# ActuatorTop.net
KiCad netlist of a schematic drawn in Altium Designer
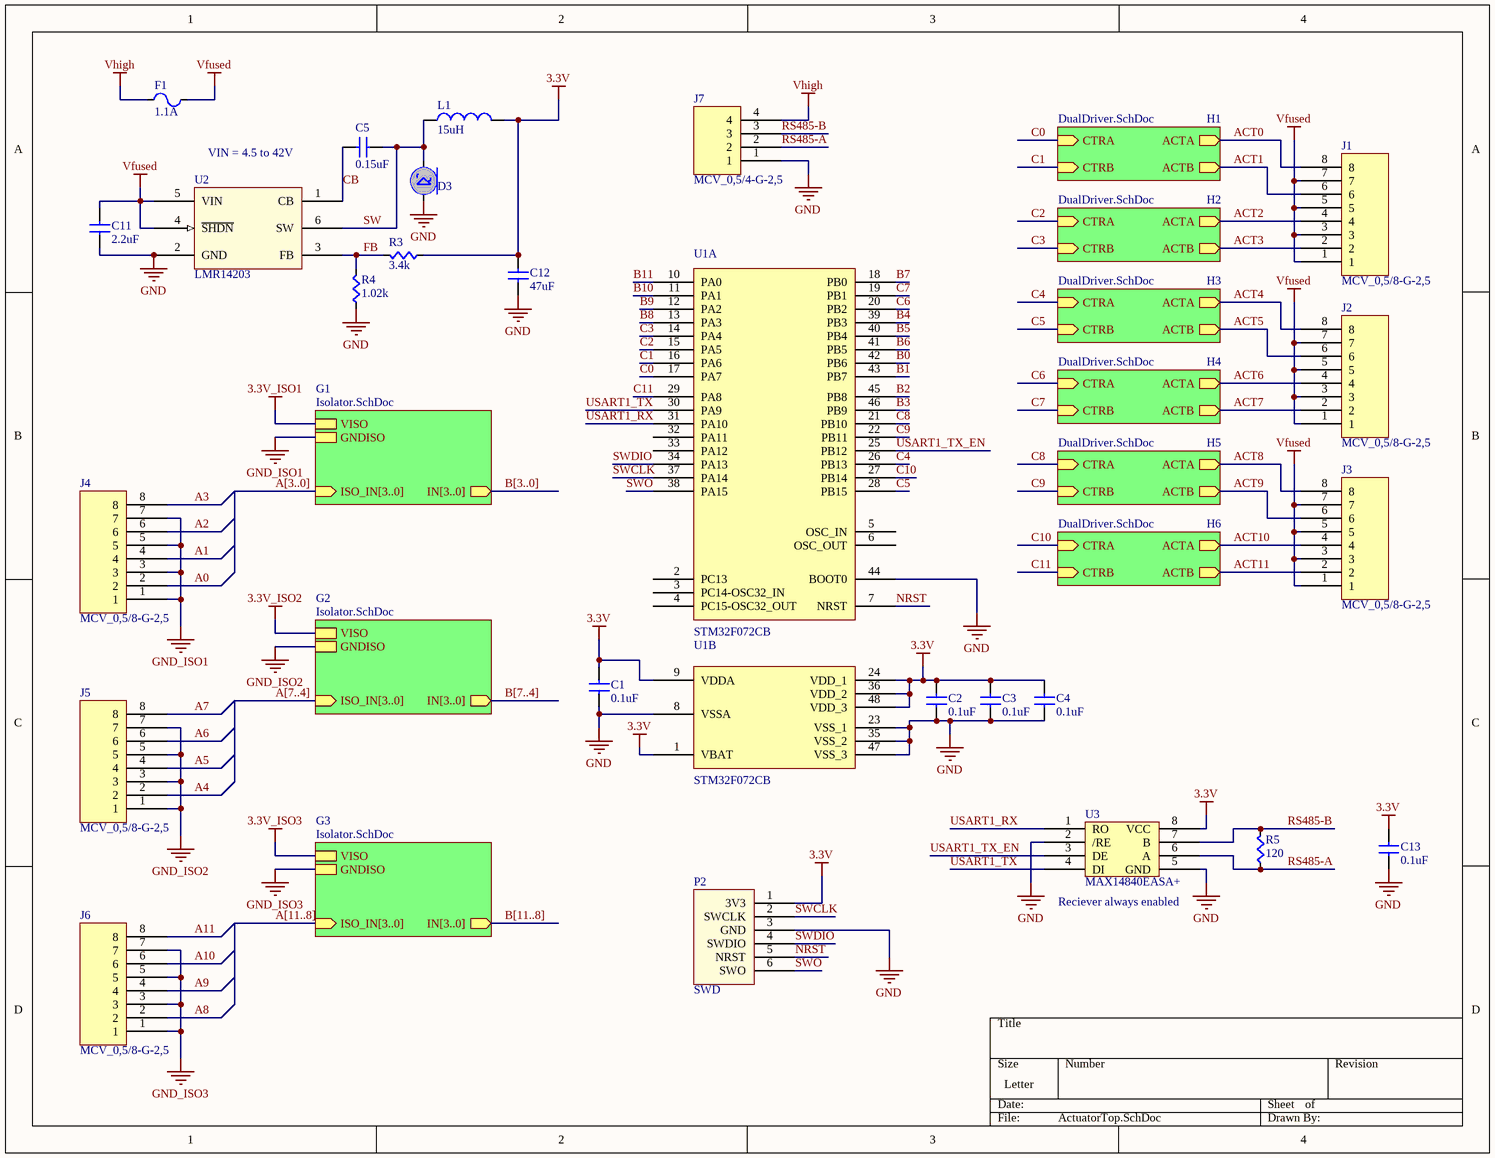
[diagram p0: ActuatorTop.SchDoc]

(export (version "E")
  (design (tool "Eeschema 10.0.6"))
  (components
    (comp (ref "C1")
      (value "0.1uF")
      (footprint "CAPC0603")
      (fields (field (name "Comment") "Cap"))
      (libsource (lib "Passives") (part "Cap"))
    )
    (comp (ref "C2")
      (value "0.1uF")
      (footprint "CAPC0603")
      (fields (field (name "Comment") "Cap"))
      (libsource (lib "Passives") (part "Cap"))
    )
    (comp (ref "C3")
      (value "0.1uF")
      (footprint "CAPC0603")
      (fields (field (name "Comment") "Cap"))
      (libsource (lib "Passives") (part "Cap"))
    )
    (comp (ref "C4")
      (value "0.1uF")
      (footprint "CAPC0603")
      (fields (field (name "Comment") "Cap"))
      (libsource (lib "Passives") (part "Cap"))
    )
    (comp (ref "C5")
      (value "0.15uF")
      (footprint "CAPC0603")
      (fields (field (name "Comment") "Cap"))
      (libsource (lib "Passives") (part "Cap"))
    )
    (comp (ref "C11")
      (value "2.2uF")
      (footprint "CAPC0805")
      (fields (field (name "Comment") "Cap"))
      (libsource (lib "Passives") (part "Cap"))
    )
    (comp (ref "C12")
      (value "47uF")
      (footprint "CAPC1206")
      (fields (field (name "Comment") "Cap"))
      (libsource (lib "Passives") (part "Cap"))
    )
    (comp (ref "C13")
      (value "0.1uF")
      (footprint "CAPC0603")
      (fields (field (name "Comment") "Cap"))
      (libsource (lib "Passives") (part "Cap"))
    )
    (comp (ref "D3")
      (value "Schottky")
      (footprint "1N5819HW-7-F")
      (description "Schottky Diode Template")
      (libsource (lib "Semiconductors") (part "Schottky"))
    )
    (comp (ref "F1")
      (value "1.1A")
      (footprint "PTC7451X11N")
      (fields (field (name "Comment") "PTC Fuse"))
      (libsource (lib "Passives") (part "PTC_Fuse"))
    )
    (comp (ref "J1")
      (value "MCV_0,5/8-G-2,5")
      (footprint "MCV_0,5/8-G-2,5")
      (description "CONN TERM BLOCK 2.50MM 8POS, Vertical, Through-Hole, 4A")
      (libsource (lib "") (part "MCV_0,5/8-G-2,5_1"))
    )
    (comp (ref "J2")
      (value "MCV_0,5/8-G-2,5")
      (footprint "MCV_0,5/8-G-2,5")
      (description "CONN TERM BLOCK 2.50MM 8POS, Vertical, Through-Hole, 4A")
      (libsource (lib "") (part "MCV_0,5/8-G-2,5_1"))
    )
    (comp (ref "J3")
      (value "MCV_0,5/8-G-2,5")
      (footprint "MCV_0,5/8-G-2,5")
      (description "CONN TERM BLOCK 2.50MM 8POS, Vertical, Through-Hole, 4A")
      (libsource (lib "") (part "MCV_0,5/8-G-2,5_1"))
    )
    (comp (ref "J4")
      (value "MCV_0,5/8-G-2,5")
      (footprint "MCV_0,5/8-G-2,5")
      (description "CONN TERM BLOCK 2.50MM 8POS, Vertical, Through-Hole, 4A")
      (libsource (lib "Connectors") (part "MCV_0,5/8-G-2,5"))
    )
    (comp (ref "J5")
      (value "MCV_0,5/8-G-2,5")
      (footprint "MCV_0,5/8-G-2,5")
      (description "CONN TERM BLOCK 2.50MM 8POS, Vertical, Through-Hole, 4A")
      (libsource (lib "Connectors") (part "MCV_0,5/8-G-2,5"))
    )
    (comp (ref "J6")
      (value "MCV_0,5/8-G-2,5")
      (footprint "MCV_0,5/8-G-2,5")
      (description "CONN TERM BLOCK 2.50MM 8POS, Vertical, Through-Hole, 4A")
      (libsource (lib "Connectors") (part "MCV_0,5/8-G-2,5"))
    )
    (comp (ref "J7")
      (value "MCV_0,5/4-G-2,5")
      (footprint "MCV_0,5/4-G-2,5")
      (description "CONN TERM BLOCK 2.50MM 4POS, Vertical, Through-Hole, 4A")
      (libsource (lib "Connectors") (part "MCV_0,5/4-G-2,5"))
    )
    (comp (ref "L1")
      (value "Inductor")
      (footprint "INDP6060X48N")
      (fields (field (name "INDUCTANCE") "15uH"))
      (libsource (lib "Passives") (part "Inductor"))
    )
    (comp (ref "P2")
      (value "SWD")
      (footprint "SWD_STM32")
      (description "SWD connector matching the pinout on STM Discovery Boards")
      (libsource (lib "Connectors") (part "SWD_STM32"))
    )
    (comp (ref "R3")
      (value "3.4k")
      (footprint "RES0603")
      (fields (field (name "Comment") "Res"))
      (libsource (lib "Passives") (part "Res"))
    )
    (comp (ref "R4")
      (value "1.02k")
      (footprint "RES0603")
      (fields (field (name "Comment") "Res"))
      (libsource (lib "Passives") (part "Res"))
    )
    (comp (ref "R5")
      (value "120")
      (footprint "RES0603")
      (fields (field (name "Comment") "Res"))
      (libsource (lib "Passives") (part "Res"))
    )
    (comp (ref "U1")
      (value "STM32F072CB")
      (footprint "STM32F072CB")
      (description "MCU 32BIT 128KB FLASH 48LQFP")
      (libsource (lib "ICs") (part "STM32F072CB"))
    )
    (comp (ref "U2")
      (value "LMR14203")
      (footprint "SOT95P280X110-6N")
      (description "Simple Switcher 42Vin 0.3A Step-Down Voltage Regulator")
      (libsource (lib "ICs") (part "LMR14203"))
    )
    (comp (ref "U3")
      (value "MAX14840EASA+")
      (footprint "MAX14840EASA+")
      (description "TXRX 40MBPS RS485/RS422 8-SOIC")
      (libsource (lib "ICs") (part "MAX14840EASA+"))
    )
  )
  (nets
    (net (code "1") (name "/A0") (class "Default")
      (node (ref "J4") (pin "2") (pinfunction "2_2") (pintype "passive"))
    )
    (net (code "2") (name "/A1") (class "Default")
      (node (ref "J4") (pin "4") (pinfunction "4_4") (pintype "passive"))
    )
    (net (code "3") (name "/A2") (class "Default")
      (node (ref "J4") (pin "6") (pinfunction "6_6") (pintype "passive"))
    )
    (net (code "4") (name "/A3") (class "Default")
      (node (ref "J4") (pin "8") (pinfunction "8_8") (pintype "passive"))
    )
    (net (code "5") (name "/A4") (class "Default")
      (node (ref "J5") (pin "2") (pinfunction "2_2") (pintype "passive"))
    )
    (net (code "6") (name "/A5") (class "Default")
      (node (ref "J5") (pin "4") (pinfunction "4_4") (pintype "passive"))
    )
    (net (code "7") (name "/A6") (class "Default")
      (node (ref "J5") (pin "6") (pinfunction "6_6") (pintype "passive"))
    )
    (net (code "8") (name "/A7") (class "Default")
      (node (ref "J5") (pin "8") (pinfunction "8_8") (pintype "passive"))
    )
    (net (code "9") (name "/A8") (class "Default")
      (node (ref "J6") (pin "2") (pinfunction "2_2") (pintype "passive"))
    )
    (net (code "10") (name "/A9") (class "Default")
      (node (ref "J6") (pin "4") (pinfunction "4_4") (pintype "passive"))
    )
    (net (code "11") (name "/A10") (class "Default")
      (node (ref "J6") (pin "6") (pinfunction "6_6") (pintype "passive"))
    )
    (net (code "12") (name "/A11") (class "Default")
      (node (ref "J6") (pin "8") (pinfunction "8_8") (pintype "passive"))
    )
    (net (code "13") (name "/ACT0") (class "Default")
      (node (ref "J1") (pin "8") (pinfunction "8_8") (pintype "passive"))
    )
    (net (code "14") (name "/ACT1") (class "Default")
      (node (ref "J1") (pin "6") (pinfunction "6_6") (pintype "passive"))
    )
    (net (code "15") (name "/ACT2") (class "Default")
      (node (ref "J1") (pin "4") (pinfunction "4_4") (pintype "passive"))
    )
    (net (code "16") (name "/ACT3") (class "Default")
      (node (ref "J1") (pin "2") (pinfunction "2_2") (pintype "passive"))
    )
    (net (code "17") (name "/ACT4") (class "Default")
      (node (ref "J2") (pin "8") (pinfunction "8_8") (pintype "passive"))
    )
    (net (code "18") (name "/ACT5") (class "Default")
      (node (ref "J2") (pin "6") (pinfunction "6_6") (pintype "passive"))
    )
    (net (code "19") (name "/ACT6") (class "Default")
      (node (ref "J2") (pin "4") (pinfunction "4_4") (pintype "passive"))
    )
    (net (code "20") (name "/ACT7") (class "Default")
      (node (ref "J2") (pin "2") (pinfunction "2_2") (pintype "passive"))
    )
    (net (code "21") (name "/ACT8") (class "Default")
      (node (ref "J3") (pin "8") (pinfunction "8_8") (pintype "passive"))
    )
    (net (code "22") (name "/ACT9") (class "Default")
      (node (ref "J3") (pin "6") (pinfunction "6_6") (pintype "passive"))
    )
    (net (code "23") (name "/ACT10") (class "Default")
      (node (ref "J3") (pin "4") (pinfunction "4_4") (pintype "passive"))
    )
    (net (code "24") (name "/ACT11") (class "Default")
      (node (ref "J3") (pin "2") (pinfunction "2_2") (pintype "passive"))
    )
    (net (code "28") (name "/B0") (class "Default")
      (node (ref "U1") (pin "42") (pinfunction "PB6_42") (pintype "passive"))
    )
    (net (code "29") (name "/B1") (class "Default")
      (node (ref "U1") (pin "43") (pinfunction "PB7_43") (pintype "passive"))
    )
    (net (code "30") (name "/B2") (class "Default")
      (node (ref "U1") (pin "45") (pinfunction "PB8_45") (pintype "passive"))
    )
    (net (code "31") (name "/B3") (class "Default")
      (node (ref "U1") (pin "46") (pinfunction "PB9_46") (pintype "passive"))
    )
    (net (code "32") (name "/B4") (class "Default")
      (node (ref "U1") (pin "39") (pinfunction "PB3_39") (pintype "passive"))
    )
    (net (code "33") (name "/B5") (class "Default")
      (node (ref "U1") (pin "40") (pinfunction "PB4_40") (pintype "passive"))
    )
    (net (code "34") (name "/B6") (class "Default")
      (node (ref "U1") (pin "41") (pinfunction "PB5_41") (pintype "passive"))
    )
    (net (code "35") (name "/B7") (class "Default")
      (node (ref "U1") (pin "18") (pinfunction "PB0_18") (pintype "passive"))
    )
    (net (code "36") (name "/B8") (class "Default")
      (node (ref "U1") (pin "13") (pinfunction "PA3_13") (pintype "passive"))
    )
    (net (code "37") (name "/B9") (class "Default")
      (node (ref "U1") (pin "12") (pinfunction "PA2_12") (pintype "passive"))
    )
    (net (code "38") (name "/B10") (class "Default")
      (node (ref "U1") (pin "11") (pinfunction "PA1_11") (pintype "passive"))
    )
    (net (code "39") (name "/B11") (class "Default")
      (node (ref "U1") (pin "10") (pinfunction "PA0_10") (pintype "passive"))
    )
    (net (code "43") (name "/C0") (class "Default")
      (node (ref "U1") (pin "17") (pinfunction "PA7_17") (pintype "passive"))
    )
    (net (code "44") (name "/C1") (class "Default")
      (node (ref "U1") (pin "16") (pinfunction "PA6_16") (pintype "passive"))
    )
    (net (code "45") (name "/C2") (class "Default")
      (node (ref "U1") (pin "15") (pinfunction "PA5_15") (pintype "passive"))
    )
    (net (code "46") (name "/C3") (class "Default")
      (node (ref "U1") (pin "14") (pinfunction "PA4_14") (pintype "passive"))
    )
    (net (code "47") (name "/C4") (class "Default")
      (node (ref "U1") (pin "26") (pinfunction "PB13_26") (pintype "passive"))
    )
    (net (code "48") (name "/C5") (class "Default")
      (node (ref "U1") (pin "28") (pinfunction "PB15_28") (pintype "passive"))
    )
    (net (code "49") (name "/C6") (class "Default")
      (node (ref "U1") (pin "20") (pinfunction "PB2_20") (pintype "passive"))
    )
    (net (code "50") (name "/C7") (class "Default")
      (node (ref "U1") (pin "19") (pinfunction "PB1_19") (pintype "passive"))
    )
    (net (code "51") (name "/C8") (class "Default")
      (node (ref "U1") (pin "21") (pinfunction "PB10_21") (pintype "passive"))
    )
    (net (code "52") (name "/C9") (class "Default")
      (node (ref "U1") (pin "22") (pinfunction "PB11_22") (pintype "passive"))
    )
    (net (code "53") (name "/C10") (class "Default")
      (node (ref "U1") (pin "27") (pinfunction "PB14_27") (pintype "passive"))
    )
    (net (code "54") (name "/C11") (class "Default")
      (node (ref "U1") (pin "29") (pinfunction "PA8_29") (pintype "passive"))
    )
    (net (code "55") (name "/CB") (class "Default")
      (node (ref "C5") (pin "1") (pinfunction "A_1") (pintype "passive"))
      (node (ref "U2") (pin "1") (pinfunction "CB_1") (pintype "passive"))
    )
    (net (code "56") (name "/FB") (class "Default")
      (node (ref "R3") (pin "1") (pinfunction "A_1") (pintype "passive"))
      (node (ref "R4") (pin "1") (pinfunction "A_1") (pintype "passive"))
      (node (ref "U2") (pin "3") (pinfunction "FB_3") (pintype "passive"))
    )
    (net (code "57") (name "/NRST") (class "Default")
      (node (ref "P2") (pin "5") (pinfunction "NRST_5") (pintype "passive"))
      (node (ref "U1") (pin "7") (pinfunction "NRST_7") (pintype "passive"))
    )
    (net (code "58") (name "/RS485-A") (class "Default")
      (node (ref "J7") (pin "2") (pinfunction "2_2") (pintype "passive"))
      (node (ref "R5") (pin "2") (pinfunction "B_2") (pintype "passive"))
      (node (ref "U3") (pin "6") (pinfunction "A_6") (pintype "passive"))
    )
    (net (code "59") (name "/RS485-B") (class "Default")
      (node (ref "J7") (pin "3") (pinfunction "3_3") (pintype "passive"))
      (node (ref "R5") (pin "1") (pinfunction "A_1") (pintype "passive"))
      (node (ref "U3") (pin "7") (pinfunction "B_7") (pintype "passive"))
    )
    (net (code "60") (name "/SW") (class "Default")
      (node (ref "C5") (pin "2") (pinfunction "B_2") (pintype "passive"))
      (node (ref "D3") (pin "C") (pinfunction "C_C") (pintype "passive"))
      (node (ref "L1") (pin "1") (pinfunction "A_1") (pintype "passive"))
      (node (ref "U2") (pin "6") (pinfunction "SW_6") (pintype "passive"))
    )
    (net (code "61") (name "/SWCLK") (class "Default")
      (node (ref "P2") (pin "2") (pinfunction "SWCLK_2") (pintype "passive"))
      (node (ref "U1") (pin "37") (pinfunction "PA14_37") (pintype "passive"))
    )
    (net (code "62") (name "/SWDIO") (class "Default")
      (node (ref "P2") (pin "4") (pinfunction "SWDIO_4") (pintype "passive"))
      (node (ref "U1") (pin "34") (pinfunction "PA13_34") (pintype "passive"))
    )
    (net (code "63") (name "/SWO") (class "Default")
      (node (ref "P2") (pin "6") (pinfunction "SWO_6") (pintype "passive"))
      (node (ref "U1") (pin "38") (pinfunction "PA15_38") (pintype "passive"))
    )
    (net (code "64") (name "/USART1_RX") (class "Default")
      (node (ref "U1") (pin "31") (pinfunction "PA10_31") (pintype "passive"))
      (node (ref "U3") (pin "1") (pinfunction "RO_1") (pintype "passive"))
    )
    (net (code "65") (name "/USART1_TX") (class "Default")
      (node (ref "U1") (pin "30") (pinfunction "PA9_30") (pintype "passive"))
      (node (ref "U3") (pin "4") (pinfunction "DI_4") (pintype "passive"))
    )
    (net (code "66") (name "/USART1_TX_EN") (class "Default")
      (node (ref "U1") (pin "25") (pinfunction "PB12_25") (pintype "passive"))
      (node (ref "U3") (pin "3") (pinfunction "DE_3") (pintype "passive"))
    )
    (net (code "67") (name "3.3V") (class "Default")
      (node (ref "C1") (pin "1") (pinfunction "A_1") (pintype "passive"))
      (node (ref "C12") (pin "2") (pinfunction "B_2") (pintype "passive"))
      (node (ref "C13") (pin "1") (pinfunction "A_1") (pintype "passive"))
      (node (ref "C2") (pin "1") (pinfunction "A_1") (pintype "passive"))
      (node (ref "C3") (pin "1") (pinfunction "A_1") (pintype "passive"))
      (node (ref "C4") (pin "1") (pinfunction "A_1") (pintype "passive"))
      (node (ref "L1") (pin "2") (pinfunction "B_2") (pintype "passive"))
      (node (ref "P2") (pin "1") (pinfunction "3V3_1") (pintype "passive"))
      (node (ref "R3") (pin "2") (pinfunction "B_2") (pintype "passive"))
      (node (ref "U1") (pin "1") (pinfunction "VBAT_1") (pintype "passive"))
      (node (ref "U1") (pin "24") (pinfunction "VDD_1_24") (pintype "passive"))
      (node (ref "U1") (pin "36") (pinfunction "VDD_2_36") (pintype "passive"))
      (node (ref "U1") (pin "48") (pinfunction "VDD_3_48") (pintype "passive"))
      (node (ref "U1") (pin "9") (pinfunction "VDDA_9") (pintype "passive"))
      (node (ref "U3") (pin "8") (pinfunction "VCC_8") (pintype "passive"))
    )
    (net (code "71") (name "GND") (class "Default")
      (node (ref "C1") (pin "2") (pinfunction "B_2") (pintype "passive"))
      (node (ref "C11") (pin "1") (pinfunction "A_1") (pintype "passive"))
      (node (ref "C12") (pin "1") (pinfunction "A_1") (pintype "passive"))
      (node (ref "C13") (pin "2") (pinfunction "B_2") (pintype "passive"))
      (node (ref "C2") (pin "2") (pinfunction "B_2") (pintype "passive"))
      (node (ref "C3") (pin "2") (pinfunction "B_2") (pintype "passive"))
      (node (ref "C4") (pin "2") (pinfunction "B_2") (pintype "passive"))
      (node (ref "D3") (pin "A") (pinfunction "A_A") (pintype "passive"))
      (node (ref "J7") (pin "1") (pinfunction "1_1") (pintype "passive"))
      (node (ref "P2") (pin "3") (pinfunction "GND_3") (pintype "passive"))
      (node (ref "R4") (pin "2") (pinfunction "B_2") (pintype "passive"))
      (node (ref "U1") (pin "23") (pinfunction "VSS_1_23") (pintype "passive"))
      (node (ref "U1") (pin "35") (pinfunction "VSS_2_35") (pintype "passive"))
      (node (ref "U1") (pin "44") (pinfunction "BOOT0_44") (pintype "passive"))
      (node (ref "U1") (pin "47") (pinfunction "VSS_3_47") (pintype "passive"))
      (node (ref "U1") (pin "8") (pinfunction "VSSA_8") (pintype "passive"))
      (node (ref "U2") (pin "2") (pinfunction "GND_2") (pintype "power_in"))
      (node (ref "U3") (pin "2") (pinfunction "/RE_2") (pintype "passive"))
      (node (ref "U3") (pin "5") (pinfunction "GND_5") (pintype "passive"))
    )
    (net (code "72") (name "GND_ISO1") (class "Default")
      (node (ref "J4") (pin "1") (pinfunction "1_1") (pintype "passive"))
      (node (ref "J4") (pin "3") (pinfunction "3_3") (pintype "passive"))
      (node (ref "J4") (pin "5") (pinfunction "5_5") (pintype "passive"))
      (node (ref "J4") (pin "7") (pinfunction "7_7") (pintype "passive"))
    )
    (net (code "73") (name "GND_ISO2") (class "Default")
      (node (ref "J5") (pin "1") (pinfunction "1_1") (pintype "passive"))
      (node (ref "J5") (pin "3") (pinfunction "3_3") (pintype "passive"))
      (node (ref "J5") (pin "5") (pinfunction "5_5") (pintype "passive"))
      (node (ref "J5") (pin "7") (pinfunction "7_7") (pintype "passive"))
    )
    (net (code "74") (name "GND_ISO3") (class "Default")
      (node (ref "J6") (pin "1") (pinfunction "1_1") (pintype "passive"))
      (node (ref "J6") (pin "3") (pinfunction "3_3") (pintype "passive"))
      (node (ref "J6") (pin "5") (pinfunction "5_5") (pintype "passive"))
      (node (ref "J6") (pin "7") (pinfunction "7_7") (pintype "passive"))
    )
    (net (code "75") (name "Vfused") (class "Default")
      (node (ref "C11") (pin "2") (pinfunction "B_2") (pintype "passive"))
      (node (ref "F1") (pin "2") (pinfunction "B_2") (pintype "passive"))
      (node (ref "J1") (pin "1") (pinfunction "1_1") (pintype "passive"))
      (node (ref "J1") (pin "3") (pinfunction "3_3") (pintype "passive"))
      (node (ref "J1") (pin "5") (pinfunction "5_5") (pintype "passive"))
      (node (ref "J1") (pin "7") (pinfunction "7_7") (pintype "passive"))
      (node (ref "J2") (pin "1") (pinfunction "1_1") (pintype "passive"))
      (node (ref "J2") (pin "3") (pinfunction "3_3") (pintype "passive"))
      (node (ref "J2") (pin "5") (pinfunction "5_5") (pintype "passive"))
      (node (ref "J2") (pin "7") (pinfunction "7_7") (pintype "passive"))
      (node (ref "J3") (pin "1") (pinfunction "1_1") (pintype "passive"))
      (node (ref "J3") (pin "3") (pinfunction "3_3") (pintype "passive"))
      (node (ref "J3") (pin "5") (pinfunction "5_5") (pintype "passive"))
      (node (ref "J3") (pin "7") (pinfunction "7_7") (pintype "passive"))
      (node (ref "U2") (pin "4") (pinfunction "~{SHDN}_4") (pintype "input"))
      (node (ref "U2") (pin "5") (pinfunction "VIN_5") (pintype "passive"))
    )
    (net (code "76") (name "Vhigh") (class "Default")
      (node (ref "F1") (pin "1") (pinfunction "A_1") (pintype "passive"))
      (node (ref "J7") (pin "4") (pinfunction "4_4") (pintype "passive"))
    )
    (net (code "77") (name "unconnected-(U1A-OSC_IN-Pad5)") (class "Default")
      (node (ref "U1") (pin "5") (pinfunction "OSC_IN_5") (pintype "passive"))
    )
    (net (code "78") (name "unconnected-(U1A-OSC_OUT-Pad6)") (class "Default")
      (node (ref "U1") (pin "6") (pinfunction "OSC_OUT_6") (pintype "passive"))
    )
    (net (code "79") (name "unconnected-(U1A-PA11-Pad32)") (class "Default")
      (node (ref "U1") (pin "32") (pinfunction "PA11_32") (pintype "passive"))
    )
    (net (code "80") (name "unconnected-(U1A-PA12-Pad33)") (class "Default")
      (node (ref "U1") (pin "33") (pinfunction "PA12_33") (pintype "passive"))
    )
    (net (code "81") (name "unconnected-(U1A-PC13-Pad2)") (class "Default")
      (node (ref "U1") (pin "2") (pinfunction "PC13_2") (pintype "passive"))
    )
    (net (code "82") (name "unconnected-(U1A-PC14-OSC32_IN-Pad3)") (class "Default")
      (node (ref "U1") (pin "3") (pinfunction "PC14-OSC32_IN_3") (pintype "passive"))
    )
    (net (code "83") (name "unconnected-(U1A-PC15-OSC32_OUT-Pad4)") (class "Default")
      (node (ref "U1") (pin "4") (pinfunction "PC15-OSC32_OUT_4") (pintype "passive"))
    )
  )
)
